# SFH7072_Breakout.net
KiCad netlist of a schematic drawn in Altium Designer
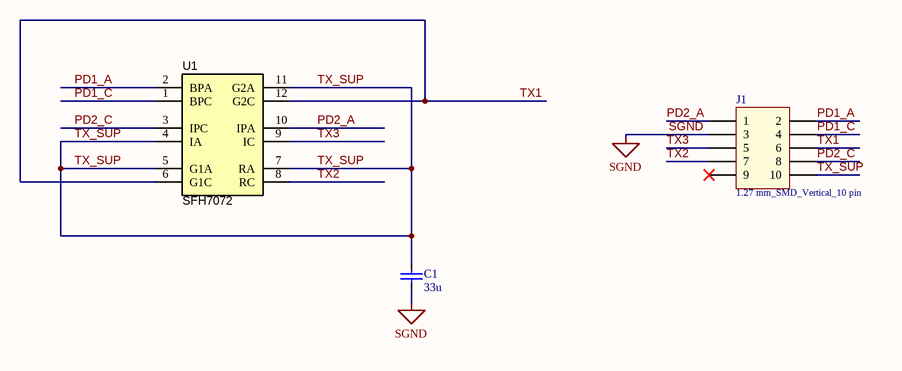
[diagram p0: SFH7072_Breakout.SchDoc]

(export (version "E")
  (design (tool "Eeschema 10.0.6"))
  (components
    (comp (ref "C1")
      (value "33u")
      (footprint "Lib_C:CAPC2012X05N")
      (description "Kondensator 10u 0402")
      (libsource (lib "Lib_C") (part "C_33u_0805"))
    )
    (comp (ref "J1")
      (value "1.27 mm_SMD_Vertical_10 pin")
      (footprint "62131021021")
      (description "Pin Header WR-PHD, pitch 1.27 mm, SMD, Vertical, dual row, 10 pin")
      (fields (field (name "PART NUMBER") "62131021021") (field (name "PUBLISHER") "Wurth Elektronik"))
      (libsource (lib "ALTIUM-PHD_2_00_THT_PIN_HEADER_6200XX11121-rev18a") (part "62131021021"))
    )
    (comp (ref "U1")
      (value "SFH7072")
      (footprint "SFH_7072")
      (description "BioMon Sensor, SMD")
      (fields
        (field (name "MANUFACTURER") "OSRAM")
        (field (name "SYMBOLCREATOR") "Altium")
        (field (name "PUBLISHER") "Texas Instruments")
      )
      (libsource (lib "Other_IC") (part "SFH7072"))
    )
  )
  (nets
    (net (code "1") (name "/PD1_A") (class "Default")
      (node (ref "J1") (pin "2") (pinfunction "2_2") (pintype "passive"))
      (node (ref "U1") (pin "2") (pinfunction "BPA_2") (pintype "passive"))
    )
    (net (code "2") (name "/PD1_C") (class "Default")
      (node (ref "J1") (pin "4") (pinfunction "4_4") (pintype "passive"))
      (node (ref "U1") (pin "1") (pinfunction "BPC_1") (pintype "passive"))
    )
    (net (code "3") (name "/PD2_A") (class "Default")
      (node (ref "J1") (pin "1") (pinfunction "1_1") (pintype "passive"))
      (node (ref "U1") (pin "10") (pinfunction "IPA_10") (pintype "passive"))
    )
    (net (code "4") (name "/PD2_C") (class "Default")
      (node (ref "J1") (pin "8") (pinfunction "8_8") (pintype "passive"))
      (node (ref "U1") (pin "3") (pinfunction "IPC_3") (pintype "passive"))
    )
    (net (code "5") (name "/TX1") (class "Default")
      (node (ref "J1") (pin "6") (pinfunction "6_6") (pintype "passive"))
      (node (ref "U1") (pin "12") (pinfunction "G2C_12") (pintype "passive"))
      (node (ref "U1") (pin "6") (pinfunction "G1C_6") (pintype "passive"))
    )
    (net (code "6") (name "/TX2") (class "Default")
      (node (ref "J1") (pin "7") (pinfunction "7_7") (pintype "passive"))
      (node (ref "U1") (pin "8") (pinfunction "RC_8") (pintype "passive"))
    )
    (net (code "7") (name "/TX3") (class "Default")
      (node (ref "J1") (pin "5") (pinfunction "5_5") (pintype "passive"))
      (node (ref "U1") (pin "9") (pinfunction "IC_9") (pintype "passive"))
    )
    (net (code "8") (name "/TX_SUP") (class "Default")
      (node (ref "C1") (pin "2") (pinfunction "2_2") (pintype "passive"))
      (node (ref "J1") (pin "10") (pinfunction "10_10") (pintype "passive"))
      (node (ref "U1") (pin "11") (pinfunction "G2A_11") (pintype "passive"))
      (node (ref "U1") (pin "4") (pinfunction "IA_4") (pintype "passive"))
      (node (ref "U1") (pin "5") (pinfunction "G1A_5") (pintype "passive"))
      (node (ref "U1") (pin "7") (pinfunction "RA_7") (pintype "passive"))
    )
    (net (code "9") (name "SGND") (class "Default")
      (node (ref "C1") (pin "1") (pinfunction "1_1") (pintype "passive"))
      (node (ref "J1") (pin "3") (pinfunction "3_3") (pintype "passive"))
    )
    (net (code "10") (name "unconnected-(J1-Pad9)") (class "Default")
      (node (ref "J1") (pin "9") (pinfunction "9_9") (pintype "passive+no_connect"))
    )
  )
)
